# arduino_uno_pcb__with_lcd.net
KiCad netlist of a schematic drawn in EAGLE
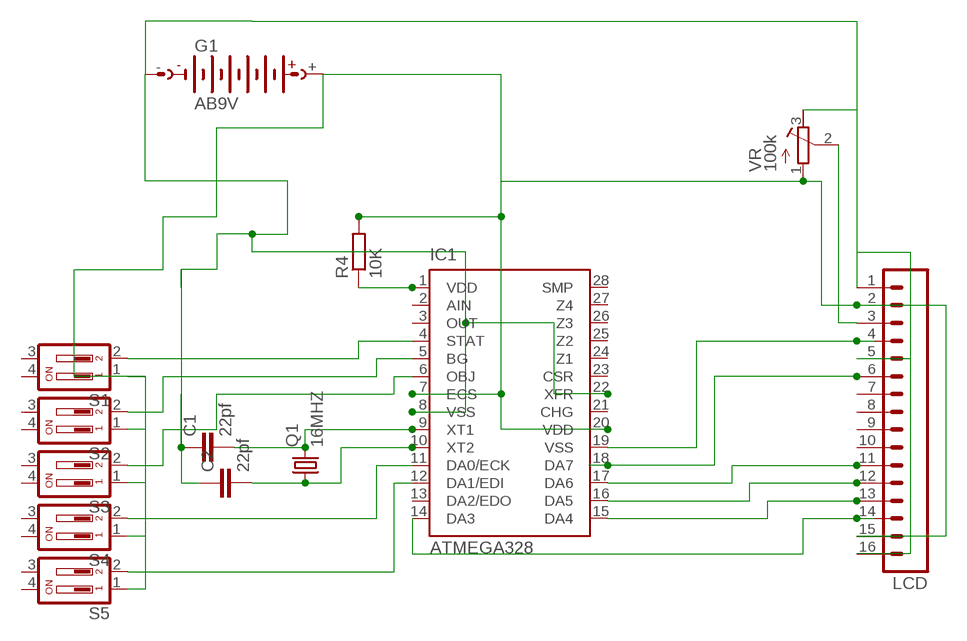
[diagram p0: schematic, sheet 1]

(export (version "E")
  (design (tool "Eeschema 10.0.6"))
  (components
    (comp (ref "C1")
      (value "22pf")
      (footprint "eagle-import:C2.5-2")
      (libsource (lib "eagle-import") (part "C2.5/2"))
    )
    (comp (ref "C2")
      (value "22pf")
      (footprint "eagle-import:C2.5-2")
      (libsource (lib "eagle-import") (part "C2.5/2"))
    )
    (comp (ref "G1")
      (value "AB9V")
      (footprint "eagle-import:AB9V")
      (libsource (lib "eagle-import") (part "AB9V"))
    )
    (comp (ref "IC1")
      (value "ATMEGA328")
      (footprint "eagle-import:DIL28-3")
      (libsource (lib "eagle-import") (part "QT9701BD"))
    )
    (comp (ref "LCD")
      (value "M16")
      (footprint "eagle-import:16P")
      (libsource (lib "eagle-import") (part "M16"))
    )
    (comp (ref "Q1")
      (value "16MHZ")
      (footprint "eagle-import:HC49_S")
      (libsource (lib "eagle-import") (part "CRYSTALHC49S"))
    )
    (comp (ref "R4")
      (value "10K")
      (footprint "eagle-import:0207_10")
      (libsource (lib "eagle-import") (part "R-EU_0207/10"))
    )
    (comp (ref "S1")
      (value "DP02")
      (footprint "eagle-import:DP-02")
      (fields (field (name "MPN") "MCDP02"))
      (libsource (lib "eagle-import") (part "DP02"))
    )
    (comp (ref "S2")
      (value "DP02")
      (footprint "eagle-import:DP-02")
      (fields
        (field (name "MPN") "MCDP02")
        (field (name "MPN_1") "MCDP02")
        (field (name "OC_FARNELL") "1255233")
        (field (name "OC_NEWARK") "26M1095")
      )
      (libsource (lib "eagle-import") (part "DP02"))
    )
    (comp (ref "S3")
      (value "DP02")
      (footprint "eagle-import:DP-02")
      (fields
        (field (name "MPN") "MCDP02")
        (field (name "MPN_1") "MCDP02")
        (field (name "OC_FARNELL") "1255233")
        (field (name "OC_NEWARK") "26M1095")
      )
      (libsource (lib "eagle-import") (part "DP02"))
    )
    (comp (ref "S4")
      (value "DP02")
      (footprint "eagle-import:DP-02")
      (fields
        (field (name "MPN") "MCDP02")
        (field (name "MPN_1") "MCDP02")
        (field (name "OC_FARNELL") "1255233")
        (field (name "OC_NEWARK") "26M1095")
      )
      (libsource (lib "eagle-import") (part "DP02"))
    )
    (comp (ref "S5")
      (value "DP02")
      (footprint "eagle-import:DP-02")
      (fields
        (field (name "MPN") "MCDP02")
        (field (name "MPN_1") "MCDP02")
        (field (name "OC_FARNELL") "1255233")
        (field (name "OC_NEWARK") "26M1095")
      )
      (libsource (lib "eagle-import") (part "DP02"))
    )
    (comp (ref "VR")
      (value "100k")
      (footprint "eagle-import:RTRIM64P")
      (libsource (lib "eagle-import") (part "R-TRIMM64P"))
    )
  )
  (nets
    (net (code "1") (name "Net-(IC1-BG)") (class "Default")
      (node (ref "IC1") (pin "5") (pinfunction "BG_5") (pintype "input"))
      (node (ref "S2") (pin "2") (pinfunction "2_2") (pintype "passive"))
    )
    (net (code "2") (name "Net-(IC1-DA0{slash}ECK)") (class "Default")
      (node (ref "IC1") (pin "11") (pinfunction "DA0/ECK_11") (pintype "output"))
      (node (ref "S4") (pin "2") (pinfunction "2_2") (pintype "passive"))
    )
    (net (code "3") (name "Net-(IC1-DA1{slash}EDI)") (class "Default")
      (node (ref "IC1") (pin "12") (pinfunction "DA1/EDI_12") (pintype "output"))
      (node (ref "S5") (pin "2") (pinfunction "2_2") (pintype "passive"))
    )
    (net (code "4") (name "Net-(IC1-DA3)") (class "Default")
      (node (ref "IC1") (pin "14") (pinfunction "DA3_14") (pintype "output"))
      (node (ref "LCD") (pin "14") (pinfunction "14_14") (pintype "passive"))
    )
    (net (code "5") (name "Net-(IC1-DA4)") (class "Default")
      (node (ref "IC1") (pin "15") (pinfunction "DA4_15") (pintype "output"))
      (node (ref "LCD") (pin "13") (pinfunction "13_13") (pintype "passive"))
    )
    (net (code "6") (name "Net-(IC1-DA5)") (class "Default")
      (node (ref "IC1") (pin "16") (pinfunction "DA5_16") (pintype "output"))
      (node (ref "LCD") (pin "12") (pinfunction "12_12") (pintype "passive"))
    )
    (net (code "7") (name "Net-(IC1-DA6)") (class "Default")
      (node (ref "IC1") (pin "17") (pinfunction "DA6_17") (pintype "output"))
      (node (ref "LCD") (pin "11") (pinfunction "11_11") (pintype "passive"))
    )
    (net (code "8") (name "Net-(IC1-DA7)") (class "Default")
      (node (ref "IC1") (pin "18") (pinfunction "DA7_18") (pintype "output"))
      (node (ref "LCD") (pin "6") (pinfunction "6_6") (pintype "passive"))
    )
    (net (code "9") (name "Net-(IC1-ECS)") (class "Default")
      (node (ref "G1") (pin "+") (pinfunction "+_+") (pintype "passive"))
      (node (ref "IC1") (pin "20") (pinfunction "VDD_20") (pintype "input"))
      (node (ref "IC1") (pin "7") (pinfunction "ECS_7") (pintype "output"))
      (node (ref "LCD") (pin "15") (pinfunction "15_15") (pintype "passive"))
      (node (ref "LCD") (pin "2") (pinfunction "2_2") (pintype "passive"))
      (node (ref "R4") (pin "2") (pinfunction "2_2") (pintype "passive"))
      (node (ref "S1") (pin "1") (pinfunction "1_1") (pintype "passive"))
      (node (ref "S2") (pin "1") (pinfunction "1_1") (pintype "passive"))
      (node (ref "S3") (pin "1") (pinfunction "1_1") (pintype "passive"))
      (node (ref "S4") (pin "1") (pinfunction "1_1") (pintype "passive"))
      (node (ref "S5") (pin "1") (pinfunction "1_1") (pintype "passive"))
      (node (ref "VR") (pin "1") (pinfunction "E_1") (pintype "passive"))
    )
    (net (code "10") (name "Net-(IC1-OBJ)") (class "Default")
      (node (ref "IC1") (pin "6") (pinfunction "OBJ_6") (pintype "input"))
      (node (ref "S3") (pin "2") (pinfunction "2_2") (pintype "passive"))
    )
    (net (code "11") (name "Net-(IC1-STAT)") (class "Default")
      (node (ref "IC1") (pin "4") (pinfunction "STAT_4") (pintype "output"))
      (node (ref "S1") (pin "2") (pinfunction "2_2") (pintype "passive"))
    )
    (net (code "12") (name "Net-(IC1-VDD-Pad1)") (class "Default")
      (node (ref "IC1") (pin "1") (pinfunction "VDD_1") (pintype "input"))
      (node (ref "R4") (pin "1") (pinfunction "1_1") (pintype "passive"))
    )
    (net (code "13") (name "Net-(IC1-VSS-Pad19)") (class "Default")
      (node (ref "IC1") (pin "19") (pinfunction "VSS_19") (pintype "input"))
      (node (ref "LCD") (pin "4") (pinfunction "4_4") (pintype "passive"))
    )
    (net (code "14") (name "Net-(IC1-XFR)") (class "Default")
      (node (ref "C1") (pin "1") (pinfunction "1_1") (pintype "passive"))
      (node (ref "C2") (pin "1") (pinfunction "1_1") (pintype "passive"))
      (node (ref "G1") (pin "-") (pinfunction "-_-") (pintype "passive"))
      (node (ref "IC1") (pin "22") (pinfunction "XFR_22") (pintype "output"))
      (node (ref "IC1") (pin "8") (pinfunction "VSS_8") (pintype "input"))
      (node (ref "LCD") (pin "1") (pinfunction "1_1") (pintype "passive"))
      (node (ref "LCD") (pin "16") (pinfunction "16_16") (pintype "passive"))
      (node (ref "LCD") (pin "5") (pinfunction "5_5") (pintype "passive"))
      (node (ref "VR") (pin "3") (pinfunction "A_3") (pintype "passive"))
    )
    (net (code "15") (name "Net-(IC1-XT1)") (class "Default")
      (node (ref "C1") (pin "2") (pinfunction "2_2") (pintype "passive"))
      (node (ref "IC1") (pin "9") (pinfunction "XT1_9") (pintype "input"))
      (node (ref "Q1") (pin "2") (pinfunction "2_2") (pintype "passive"))
    )
    (net (code "16") (name "Net-(IC1-XT2)") (class "Default")
      (node (ref "C2") (pin "2") (pinfunction "2_2") (pintype "passive"))
      (node (ref "IC1") (pin "10") (pinfunction "XT2_10") (pintype "output"))
      (node (ref "Q1") (pin "1") (pinfunction "1_1") (pintype "passive"))
    )
    (net (code "17") (name "Net-(VR-S)") (class "Default")
      (node (ref "LCD") (pin "3") (pinfunction "3_3") (pintype "passive"))
      (node (ref "VR") (pin "2") (pinfunction "S_2") (pintype "passive"))
    )
    (net (code "18") (name "unconnected-(IC1-AIN-Pad2)") (class "Default")
      (node (ref "IC1") (pin "2") (pinfunction "AIN_2") (pintype "input"))
    )
    (net (code "19") (name "unconnected-(IC1-CHG-Pad21)") (class "Default")
      (node (ref "IC1") (pin "21") (pinfunction "CHG_21") (pintype "output"))
    )
    (net (code "20") (name "unconnected-(IC1-CSR-Pad23)") (class "Default")
      (node (ref "IC1") (pin "23") (pinfunction "CSR_23") (pintype "output"))
    )
    (net (code "21") (name "unconnected-(IC1-DA2{slash}EDO-Pad13)") (class "Default")
      (node (ref "IC1") (pin "13") (pinfunction "DA2/EDO_13") (pintype "output"))
    )
    (net (code "22") (name "unconnected-(IC1-OUT-Pad3)") (class "Default")
      (node (ref "IC1") (pin "3") (pinfunction "OUT_3") (pintype "output"))
    )
    (net (code "23") (name "unconnected-(IC1-SMP-Pad28)") (class "Default")
      (node (ref "IC1") (pin "28") (pinfunction "SMP_28") (pintype "output"))
    )
    (net (code "24") (name "unconnected-(IC1-Z1-Pad24)") (class "Default")
      (node (ref "IC1") (pin "24") (pinfunction "Z1_24") (pintype "output"))
    )
    (net (code "25") (name "unconnected-(IC1-Z2-Pad25)") (class "Default")
      (node (ref "IC1") (pin "25") (pinfunction "Z2_25") (pintype "output"))
    )
    (net (code "26") (name "unconnected-(IC1-Z3-Pad26)") (class "Default")
      (node (ref "IC1") (pin "26") (pinfunction "Z3_26") (pintype "output"))
    )
    (net (code "27") (name "unconnected-(IC1-Z4-Pad27)") (class "Default")
      (node (ref "IC1") (pin "27") (pinfunction "Z4_27") (pintype "output"))
    )
    (net (code "28") (name "unconnected-(LCD-Pad7)") (class "Default")
      (node (ref "LCD") (pin "7") (pinfunction "7_7") (pintype "passive"))
    )
    (net (code "29") (name "unconnected-(LCD-Pad8)") (class "Default")
      (node (ref "LCD") (pin "8") (pinfunction "8_8") (pintype "passive"))
    )
    (net (code "30") (name "unconnected-(LCD-Pad9)") (class "Default")
      (node (ref "LCD") (pin "9") (pinfunction "9_9") (pintype "passive"))
    )
    (net (code "31") (name "unconnected-(LCD-Pad10)") (class "Default")
      (node (ref "LCD") (pin "10") (pinfunction "10_10") (pintype "passive"))
    )
    (net (code "32") (name "unconnected-(S1-Pad3)") (class "Default")
      (node (ref "S1") (pin "3") (pinfunction "3_3") (pintype "passive"))
    )
    (net (code "33") (name "unconnected-(S1-Pad4)") (class "Default")
      (node (ref "S1") (pin "4") (pinfunction "4_4") (pintype "passive"))
    )
    (net (code "34") (name "unconnected-(S2-Pad3)") (class "Default")
      (node (ref "S2") (pin "3") (pinfunction "3_3") (pintype "passive"))
    )
    (net (code "35") (name "unconnected-(S2-Pad4)") (class "Default")
      (node (ref "S2") (pin "4") (pinfunction "4_4") (pintype "passive"))
    )
    (net (code "36") (name "unconnected-(S3-Pad3)") (class "Default")
      (node (ref "S3") (pin "3") (pinfunction "3_3") (pintype "passive"))
    )
    (net (code "37") (name "unconnected-(S3-Pad4)") (class "Default")
      (node (ref "S3") (pin "4") (pinfunction "4_4") (pintype "passive"))
    )
    (net (code "38") (name "unconnected-(S4-Pad3)") (class "Default")
      (node (ref "S4") (pin "3") (pinfunction "3_3") (pintype "passive"))
    )
    (net (code "39") (name "unconnected-(S4-Pad4)") (class "Default")
      (node (ref "S4") (pin "4") (pinfunction "4_4") (pintype "passive"))
    )
    (net (code "40") (name "unconnected-(S5-Pad3)") (class "Default")
      (node (ref "S5") (pin "3") (pinfunction "3_3") (pintype "passive"))
    )
    (net (code "41") (name "unconnected-(S5-Pad4)") (class "Default")
      (node (ref "S5") (pin "4") (pinfunction "4_4") (pintype "passive"))
    )
  )
)
